# DevModule.net
KiCad netlist of a schematic drawn in Altium Designer
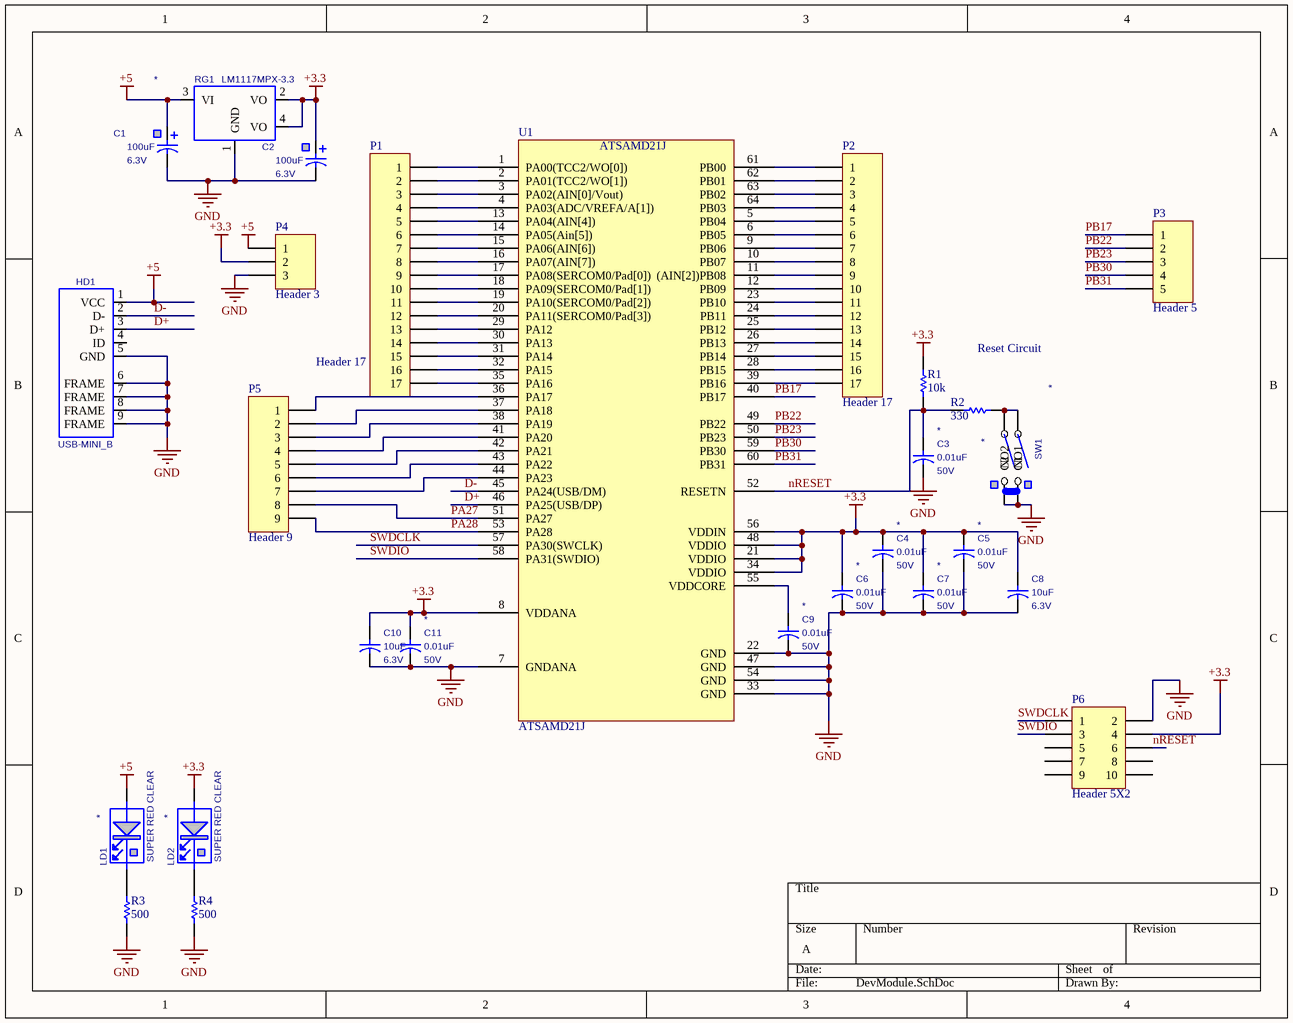
[diagram p0: DevModule.SchDoc]

(export (version "E")
  (design (tool "Eeschema 10.0.6"))
  (components
    (comp (ref "C1")
      (value "100uF")
      (footprint "100uF_6.3V_Tant_0805")
      (description "Capacitor")
      (fields
        (field (name "TOLERANCE") "+/- 20%")
        (field (name "VOLTAGE") "6.3V")
        (field (name "Comment") "100UF_TANT_6.3V_0805")
        (field (name "CHECKEDBY") "Sam Rhoufiry")
      )
      (libsource (lib "C") (part "100UF_TANT_6.3V_0805"))
    )
    (comp (ref "C2")
      (value "100uF")
      (footprint "100uF_6.3V_Tant_0805")
      (description "Capacitor")
      (fields
        (field (name "TOLERANCE") "+/- 20%")
        (field (name "VOLTAGE") "6.3V")
        (field (name "Comment") "100UF_TANT_6.3V_0805")
        (field (name "CHECKEDBY") "Sam Rhoufiry")
      )
      (libsource (lib "C") (part "100UF_TANT_6.3V_0805"))
    )
    (comp (ref "C3")
      (value "0.01uF")
      (footprint "RC0603REFLOW-IPC")
      (description "Capacitor")
      (fields
        (field (name "TOLERANCE") "+/- 10%")
        (field (name "DNS") "*")
        (field (name "VOLTAGE") "50V")
        (field (name "Comment") "0.01UF_0603REFLOW")
        (field (name "CHECKEDBY") "*")
      )
      (libsource (lib "C") (part "0.01UF_0603REFLOW"))
    )
    (comp (ref "C4")
      (value "0.01uF")
      (footprint "RC0603REFLOW-IPC")
      (description "Capacitor")
      (fields
        (field (name "TOLERANCE") "+/- 10%")
        (field (name "DNS") "*")
        (field (name "VOLTAGE") "50V")
        (field (name "Comment") "0.01UF_0603REFLOW")
        (field (name "CHECKEDBY") "*")
      )
      (libsource (lib "C") (part "0.01UF_0603REFLOW"))
    )
    (comp (ref "C5")
      (value "0.01uF")
      (footprint "RC0603REFLOW-IPC")
      (description "Capacitor")
      (fields
        (field (name "TOLERANCE") "+/- 10%")
        (field (name "DNS") "*")
        (field (name "VOLTAGE") "50V")
        (field (name "Comment") "0.01UF_0603REFLOW")
        (field (name "CHECKEDBY") "*")
      )
      (libsource (lib "C") (part "0.01UF_0603REFLOW"))
    )
    (comp (ref "C6")
      (value "0.01uF")
      (footprint "RC0603REFLOW-IPC")
      (description "Capacitor")
      (fields
        (field (name "TOLERANCE") "+/- 10%")
        (field (name "DNS") "*")
        (field (name "VOLTAGE") "50V")
        (field (name "Comment") "0.01UF_0603REFLOW")
        (field (name "CHECKEDBY") "*")
      )
      (libsource (lib "C") (part "0.01UF_0603REFLOW"))
    )
    (comp (ref "C7")
      (value "0.01uF")
      (footprint "RC0603REFLOW-IPC")
      (description "Capacitor")
      (fields
        (field (name "TOLERANCE") "+/- 10%")
        (field (name "DNS") "*")
        (field (name "VOLTAGE") "50V")
        (field (name "Comment") "0.01UF_0603REFLOW")
        (field (name "CHECKEDBY") "*")
      )
      (libsource (lib "C") (part "0.01UF_0603REFLOW"))
    )
    (comp (ref "C8")
      (value "10uF")
      (footprint "1206_NP_CAP")
      (fields
        (field (name "TOLERANCE") "-20%, +80%")
        (field (name "VOLTAGE") "6.3V")
        (field (name "Comment") "10uF_Ceramic_6.3V")
        (field (name "CHECKEDBY") "gdeguzman")
        (field (name "LASTUPDATEDBY") "Mike Tyger")
      )
      (libsource (lib "bome") (part "10uF_Ceramic_6.3V"))
    )
    (comp (ref "C9")
      (value "0.01uF")
      (footprint "RC0603REFLOW-IPC")
      (description "Capacitor")
      (fields
        (field (name "TOLERANCE") "+/- 10%")
        (field (name "DNS") "*")
        (field (name "VOLTAGE") "50V")
        (field (name "Comment") "0.01UF_0603REFLOW")
        (field (name "CHECKEDBY") "*")
      )
      (libsource (lib "C") (part "0.01UF_0603REFLOW"))
    )
    (comp (ref "C10")
      (value "10uF")
      (footprint "1206_NP_CAP")
      (fields
        (field (name "TOLERANCE") "-20%, +80%")
        (field (name "VOLTAGE") "6.3V")
        (field (name "Comment") "10uF_Ceramic_6.3V")
        (field (name "CHECKEDBY") "gdeguzman")
        (field (name "LASTUPDATEDBY") "Mike Tyger")
      )
      (libsource (lib "bome") (part "10uF_Ceramic_6.3V"))
    )
    (comp (ref "C11")
      (value "0.01uF")
      (footprint "RC0603REFLOW-IPC")
      (description "Capacitor")
      (fields
        (field (name "TOLERANCE") "+/- 10%")
        (field (name "DNS") "*")
        (field (name "VOLTAGE") "50V")
        (field (name "Comment") "0.01UF_0603REFLOW")
        (field (name "CHECKEDBY") "*")
      )
      (libsource (lib "C") (part "0.01UF_0603REFLOW"))
    )
    (comp (ref "HD1")
      (value "USB-MINI_B")
      (footprint "HD_USB_MINI_B")
      (description "Header")
      (fields (field (name "CHECKEDBY") "T. Hayes"))
      (libsource (lib "HD") (part "USB-MINI_B"))
    )
    (comp (ref "LD1")
      (value "0603_RED")
      (footprint "LED0603REFLOW-IPC-COLOR")
      (description "LED")
      (fields
        (field (name "DNS") "*")
        (field (name "COLOR") "SUPER RED CLEAR")
        (field (name "CHECKEDBY") "Elton John")
      )
      (libsource (lib "bome") (part "0603_RED"))
    )
    (comp (ref "LD2")
      (value "0603_RED")
      (footprint "LED0603REFLOW-IPC-COLOR")
      (description "LED")
      (fields
        (field (name "DNS") "*")
        (field (name "COLOR") "SUPER RED CLEAR")
        (field (name "CHECKEDBY") "Elton John")
      )
      (libsource (lib "bome") (part "0603_RED"))
    )
    (comp (ref "P1")
      (value "Header 17")
      (footprint "HDR1X17")
      (description "Header, 17-Pin")
      (fields (field (name "PUBLISHER") "Altium Limited"))
      (libsource (lib "") (part "Header 17_1"))
    )
    (comp (ref "P2")
      (value "Header 17")
      (footprint "HDR1X17")
      (description "Header, 17-Pin")
      (fields (field (name "PUBLISHER") "Altium Limited"))
      (libsource (lib "Miscellaneous Connectors") (part "Header 17"))
    )
    (comp (ref "P3")
      (value "Header 5")
      (footprint "HDR1X5")
      (description "Header, 5-Pin")
      (fields (field (name "PUBLISHER") "Altium Limited"))
      (libsource (lib "Miscellaneous Connectors") (part "Header 5"))
    )
    (comp (ref "P4")
      (value "Header 3")
      (footprint "HDR1X3")
      (description "Header, 3-Pin")
      (fields (field (name "PUBLISHER") "Altium Limited"))
      (libsource (lib "Miscellaneous Connectors") (part "Header 3"))
    )
    (comp (ref "P5")
      (value "Header 9")
      (footprint "HDR1X9")
      (description "Header, 9-Pin")
      (fields (field (name "PUBLISHER") "Altium Limited"))
      (libsource (lib "Miscellaneous Connectors") (part "Header 9"))
    )
    (comp (ref "P6")
      (value "Header 5X2")
      (footprint "HDR2X5")
      (description "Header, 5-Pin, Dual row")
      (fields (field (name "PUBLISHER") "Altium Limited"))
      (libsource (lib "Miscellaneous Connectors") (part "Header 5X2"))
    )
    (comp (ref "R1")
      (value "10k")
      (footprint "RESC2012L")
      (description "Semiconductor Resistor")
      (fields (field (name "Comment") "Res Semi") (field (name "PUBLISHER") "Altium Limited"))
      (libsource (lib "Miscellaneous Devices") (part "Res Semi"))
    )
    (comp (ref "R2")
      (value "330")
      (footprint "RESC2012L")
      (description "Semiconductor Resistor")
      (fields (field (name "Comment") "Res Semi") (field (name "PUBLISHER") "Altium Limited"))
      (libsource (lib "Miscellaneous Devices") (part "Res Semi"))
    )
    (comp (ref "R3")
      (value "500")
      (footprint "RESC2012L")
      (description "Semiconductor Resistor")
      (fields (field (name "Comment") "Res Semi") (field (name "PUBLISHER") "Altium Limited"))
      (libsource (lib "Miscellaneous Devices") (part "Res Semi"))
    )
    (comp (ref "R4")
      (value "500")
      (footprint "RESC2012L")
      (description "Semiconductor Resistor")
      (fields (field (name "Comment") "Res Semi") (field (name "PUBLISHER") "Altium Limited"))
      (libsource (lib "Miscellaneous Devices") (part "Res Semi"))
    )
    (comp (ref "RG1")
      (value "LM1117MPX-3.3")
      (footprint "SOT223REFLOW")
      (description "Regulator")
      (fields
        (field (name "VOLTAGE") "3.3V")
        (field (name "DNS") "*")
        (field (name "Comment") "LM1117SPX-3.3_SOT223")
        (field (name "CHECKEDBY") "B. Lyon")
      )
      (libsource (lib "RG") (part "LM1117SPX-3.3_SOT223"))
    )
    (comp (ref "SW1")
      (value "SW-PCB-4P-6MM")
      (footprint "SW-PCB-4PIN")
      (description "Switch")
      (fields (field (name "DNS") "*") (field (name "ALTIUM_VALUE") "*") (field (name "CHECKEDBY") "*"))
      (libsource (lib "SW") (part "SW-PCB-4P-6MM"))
    )
    (comp (ref "U1")
      (value "ATSAMD21J")
      (footprint "64-TQFP")
      (libsource (lib "mainBoardLib") (part "ATSAMD21J"))
    )
  )
  (nets
    (net (code "1") (name "+3.3") (class "Default")
      (node (ref "C10") (pin "1") (pinfunction "pin1_1") (pintype "passive"))
      (node (ref "C11") (pin "1") (pinfunction "pin1_1") (pintype "passive"))
      (node (ref "C2") (pin "1") (pinfunction "+_1") (pintype "passive"))
      (node (ref "C4") (pin "1") (pinfunction "pin1_1") (pintype "passive"))
      (node (ref "C5") (pin "1") (pinfunction "pin1_1") (pintype "passive"))
      (node (ref "C6") (pin "1") (pinfunction "pin1_1") (pintype "passive"))
      (node (ref "C7") (pin "1") (pinfunction "pin1_1") (pintype "passive"))
      (node (ref "C8") (pin "1") (pinfunction "pin1_1") (pintype "passive"))
      (node (ref "LD2") (pin "2") (pinfunction "ANODE_2") (pintype "passive"))
      (node (ref "P4") (pin "2") (pinfunction "2_2") (pintype "passive"))
      (node (ref "P6") (pin "4") (pinfunction "4_4") (pintype "passive"))
      (node (ref "R1") (pin "2") (pinfunction "2_2") (pintype "passive"))
      (node (ref "RG1") (pin "2") (pinfunction "VO_2") (pintype "passive"))
      (node (ref "RG1") (pin "4") (pinfunction "VO_4") (pintype "passive"))
      (node (ref "U1") (pin "21") (pinfunction "VDDIO_21") (pintype "passive"))
      (node (ref "U1") (pin "34") (pinfunction "VDDIO_34") (pintype "passive"))
      (node (ref "U1") (pin "48") (pinfunction "VDDIO_48") (pintype "passive"))
      (node (ref "U1") (pin "56") (pinfunction "VDDIN_56") (pintype "passive"))
      (node (ref "U1") (pin "8") (pinfunction "VDDANA_8") (pintype "passive"))
    )
    (net (code "2") (name "+5") (class "Default")
      (node (ref "C1") (pin "1") (pinfunction "+_1") (pintype "passive"))
      (node (ref "HD1") (pin "1") (pinfunction "VCC_1") (pintype "passive"))
      (node (ref "LD1") (pin "2") (pinfunction "ANODE_2") (pintype "passive"))
      (node (ref "P4") (pin "1") (pinfunction "1_1") (pintype "passive"))
      (node (ref "RG1") (pin "3") (pinfunction "VI_3") (pintype "passive"))
    )
    (net (code "3") (name "/D+") (class "Default")
      (node (ref "HD1") (pin "3") (pinfunction "D+_3") (pintype "passive"))
      (node (ref "U1") (pin "46") (pinfunction "PA25(USB/DP)_46") (pintype "passive"))
    )
    (net (code "4") (name "/D-") (class "Default")
      (node (ref "HD1") (pin "2") (pinfunction "D-_2") (pintype "passive"))
      (node (ref "U1") (pin "45") (pinfunction "PA24(USB/DM)_45") (pintype "passive"))
    )
    (net (code "5") (name "/PA27") (class "Default")
      (node (ref "P5") (pin "8") (pinfunction "8_8") (pintype "passive"))
      (node (ref "U1") (pin "51") (pinfunction "PA27_51") (pintype "passive"))
    )
    (net (code "6") (name "/PA28") (class "Default")
      (node (ref "P5") (pin "9") (pinfunction "9_9") (pintype "passive"))
      (node (ref "U1") (pin "53") (pinfunction "PA28_53") (pintype "passive"))
    )
    (net (code "7") (name "/PB17") (class "Default")
      (node (ref "P3") (pin "1") (pinfunction "1_1") (pintype "passive"))
      (node (ref "U1") (pin "40") (pinfunction "PB17_40") (pintype "passive"))
    )
    (net (code "8") (name "/PB22") (class "Default")
      (node (ref "P3") (pin "2") (pinfunction "2_2") (pintype "passive"))
      (node (ref "U1") (pin "49") (pinfunction "PB22_49") (pintype "passive"))
    )
    (net (code "9") (name "/PB23") (class "Default")
      (node (ref "P3") (pin "3") (pinfunction "3_3") (pintype "passive"))
      (node (ref "U1") (pin "50") (pinfunction "PB23_50") (pintype "passive"))
    )
    (net (code "10") (name "/PB30") (class "Default")
      (node (ref "P3") (pin "4") (pinfunction "4_4") (pintype "passive"))
      (node (ref "U1") (pin "59") (pinfunction "PB30_59") (pintype "passive"))
    )
    (net (code "11") (name "/PB31") (class "Default")
      (node (ref "P3") (pin "5") (pinfunction "5_5") (pintype "passive"))
      (node (ref "U1") (pin "60") (pinfunction "PB31_60") (pintype "passive"))
    )
    (net (code "12") (name "/SWDCLK") (class "Default")
      (node (ref "P6") (pin "1") (pinfunction "1_1") (pintype "passive"))
      (node (ref "U1") (pin "57") (pinfunction "PA30(SWCLK)_57") (pintype "passive"))
    )
    (net (code "13") (name "/SWDIO") (class "Default")
      (node (ref "P6") (pin "3") (pinfunction "3_3") (pintype "passive"))
      (node (ref "U1") (pin "58") (pinfunction "PA31(SWDIO)_58") (pintype "passive"))
    )
    (net (code "14") (name "/nRESET") (class "Default")
      (node (ref "C3") (pin "1") (pinfunction "pin1_1") (pintype "passive"))
      (node (ref "P6") (pin "6") (pinfunction "6_6") (pintype "passive"))
      (node (ref "R1") (pin "1") (pinfunction "1_1") (pintype "passive"))
      (node (ref "R2") (pin "1") (pinfunction "1_1") (pintype "passive"))
      (node (ref "U1") (pin "52") (pinfunction "RESETN_52") (pintype "passive"))
    )
    (net (code "15") (name "GND") (class "Default")
      (node (ref "C1") (pin "2") (pinfunction "-_2") (pintype "passive"))
      (node (ref "C10") (pin "2") (pinfunction "pin2_2") (pintype "passive"))
      (node (ref "C11") (pin "2") (pinfunction "pin2_2") (pintype "passive"))
      (node (ref "C2") (pin "2") (pinfunction "-_2") (pintype "passive"))
      (node (ref "C3") (pin "2") (pinfunction "pin2_2") (pintype "passive"))
      (node (ref "C4") (pin "2") (pinfunction "pin2_2") (pintype "passive"))
      (node (ref "C5") (pin "2") (pinfunction "pin2_2") (pintype "passive"))
      (node (ref "C6") (pin "2") (pinfunction "pin2_2") (pintype "passive"))
      (node (ref "C7") (pin "2") (pinfunction "pin2_2") (pintype "passive"))
      (node (ref "C8") (pin "2") (pinfunction "pin2_2") (pintype "passive"))
      (node (ref "C9") (pin "2") (pinfunction "pin2_2") (pintype "passive"))
      (node (ref "HD1") (pin "5") (pinfunction "GND_5") (pintype "passive"))
      (node (ref "HD1") (pin "6") (pinfunction "FRAME_6") (pintype "passive"))
      (node (ref "HD1") (pin "7") (pinfunction "FRAME_7") (pintype "passive"))
      (node (ref "HD1") (pin "8") (pinfunction "FRAME_8") (pintype "passive"))
      (node (ref "HD1") (pin "9") (pinfunction "FRAME_9") (pintype "passive"))
      (node (ref "P4") (pin "3") (pinfunction "3_3") (pintype "passive"))
      (node (ref "P6") (pin "2") (pinfunction "2_2") (pintype "passive"))
      (node (ref "R3") (pin "1") (pinfunction "1_1") (pintype "passive"))
      (node (ref "R4") (pin "1") (pinfunction "1_1") (pintype "passive"))
      (node (ref "RG1") (pin "1") (pinfunction "GND_1") (pintype "passive"))
      (node (ref "SW1") (pin "1") (pinfunction "C1_1") (pintype "passive"))
      (node (ref "SW1") (pin "2") (pinfunction "C2_2") (pintype "passive"))
      (node (ref "U1") (pin "22") (pinfunction "GND_22") (pintype "passive"))
      (node (ref "U1") (pin "33") (pinfunction "GND_33") (pintype "passive"))
      (node (ref "U1") (pin "47") (pinfunction "GND_47") (pintype "passive"))
      (node (ref "U1") (pin "54") (pinfunction "GND_54") (pintype "passive"))
      (node (ref "U1") (pin "7") (pinfunction "GNDANA_7") (pintype "passive"))
    )
    (net (code "16") (name "Net-(C9-pin1)") (class "Default")
      (node (ref "C9") (pin "1") (pinfunction "pin1_1") (pintype "passive"))
      (node (ref "U1") (pin "55") (pinfunction "VDDCORE_55") (pintype "passive"))
    )
    (net (code "17") (name "Net-(LD1-CATHODE)") (class "Default")
      (node (ref "LD1") (pin "1") (pinfunction "CATHODE_1") (pintype "passive"))
      (node (ref "R3") (pin "2") (pinfunction "2_2") (pintype "passive"))
    )
    (net (code "18") (name "Net-(LD2-CATHODE)") (class "Default")
      (node (ref "LD2") (pin "1") (pinfunction "CATHODE_1") (pintype "passive"))
      (node (ref "R4") (pin "2") (pinfunction "2_2") (pintype "passive"))
    )
    (net (code "19") (name "Net-(SW1-NO1)") (class "Default")
      (node (ref "R2") (pin "2") (pinfunction "2_2") (pintype "passive"))
      (node (ref "SW1") (pin "3") (pinfunction "NO2_3") (pintype "passive"))
      (node (ref "SW1") (pin "4") (pinfunction "NO1_4") (pintype "passive"))
    )
    (net (code "20") (name "Net-(U1-(AIN[2])PB08)") (class "Default")
      (node (ref "P2") (pin "9") (pinfunction "9_9") (pintype "passive"))
      (node (ref "U1") (pin "11") (pinfunction "(AIN[2])PB08_11") (pintype "passive"))
    )
    (net (code "21") (name "Net-(U1-PA00(TCC2{slash}WO[0]))") (class "Default")
      (node (ref "P1") (pin "1") (pinfunction "1_1") (pintype "passive"))
      (node (ref "U1") (pin "1") (pinfunction "PA00(TCC2/WO[0])_1") (pintype "passive"))
    )
    (net (code "22") (name "Net-(U1-PA01(TCC2{slash}WO[1]))") (class "Default")
      (node (ref "P1") (pin "2") (pinfunction "2_2") (pintype "passive"))
      (node (ref "U1") (pin "2") (pinfunction "PA01(TCC2/WO[1])_2") (pintype "passive"))
    )
    (net (code "23") (name "Net-(U1-PA02(AIN[0]{slash}Vout))") (class "Default")
      (node (ref "P1") (pin "3") (pinfunction "3_3") (pintype "passive"))
      (node (ref "U1") (pin "3") (pinfunction "PA02(AIN[0]/Vout)_3") (pintype "passive"))
    )
    (net (code "24") (name "Net-(U1-PA03(ADC{slash}VREFA{slash}A[1]))") (class "Default")
      (node (ref "P1") (pin "4") (pinfunction "4_4") (pintype "passive"))
      (node (ref "U1") (pin "4") (pinfunction "PA03(ADC/VREFA/A[1])_4") (pintype "passive"))
    )
    (net (code "25") (name "Net-(U1-PA04(AIN[4]))") (class "Default")
      (node (ref "P1") (pin "5") (pinfunction "5_5") (pintype "passive"))
      (node (ref "U1") (pin "13") (pinfunction "PA04(AIN[4])_13") (pintype "passive"))
    )
    (net (code "26") (name "Net-(U1-PA05(Ain[5]))") (class "Default")
      (node (ref "P1") (pin "6") (pinfunction "6_6") (pintype "passive"))
      (node (ref "U1") (pin "14") (pinfunction "PA05(Ain[5])_14") (pintype "passive"))
    )
    (net (code "27") (name "Net-(U1-PA06(AIN[6]))") (class "Default")
      (node (ref "P1") (pin "7") (pinfunction "7_7") (pintype "passive"))
      (node (ref "U1") (pin "15") (pinfunction "PA06(AIN[6])_15") (pintype "passive"))
    )
    (net (code "28") (name "Net-(U1-PA07(AIN[7]))") (class "Default")
      (node (ref "P1") (pin "8") (pinfunction "8_8") (pintype "passive"))
      (node (ref "U1") (pin "16") (pinfunction "PA07(AIN[7])_16") (pintype "passive"))
    )
    (net (code "29") (name "Net-(U1-PA08(SERCOM0{slash}Pad[0]))") (class "Default")
      (node (ref "P1") (pin "9") (pinfunction "9_9") (pintype "passive"))
      (node (ref "U1") (pin "17") (pinfunction "PA08(SERCOM0/Pad[0])_17") (pintype "passive"))
    )
    (net (code "30") (name "Net-(U1-PA09(SERCOM0{slash}Pad[1]))") (class "Default")
      (node (ref "P1") (pin "10") (pinfunction "10_10") (pintype "passive"))
      (node (ref "U1") (pin "18") (pinfunction "PA09(SERCOM0/Pad[1])_18") (pintype "passive"))
    )
    (net (code "31") (name "Net-(U1-PA10(SERCOM0{slash}Pad[2]))") (class "Default")
      (node (ref "P1") (pin "11") (pinfunction "11_11") (pintype "passive"))
      (node (ref "U1") (pin "19") (pinfunction "PA10(SERCOM0/Pad[2])_19") (pintype "passive"))
    )
    (net (code "32") (name "Net-(U1-PA11(SERCOM0{slash}Pad[3]))") (class "Default")
      (node (ref "P1") (pin "12") (pinfunction "12_12") (pintype "passive"))
      (node (ref "U1") (pin "20") (pinfunction "PA11(SERCOM0/Pad[3])_20") (pintype "passive"))
    )
    (net (code "33") (name "Net-(U1-PA12)") (class "Default")
      (node (ref "P1") (pin "13") (pinfunction "13_13") (pintype "passive"))
      (node (ref "U1") (pin "29") (pinfunction "PA12_29") (pintype "passive"))
    )
    (net (code "34") (name "Net-(U1-PA13)") (class "Default")
      (node (ref "P1") (pin "14") (pinfunction "14_14") (pintype "passive"))
      (node (ref "U1") (pin "30") (pinfunction "PA13_30") (pintype "passive"))
    )
    (net (code "35") (name "Net-(U1-PA14)") (class "Default")
      (node (ref "P1") (pin "15") (pinfunction "15_15") (pintype "passive"))
      (node (ref "U1") (pin "31") (pinfunction "PA14_31") (pintype "passive"))
    )
    (net (code "36") (name "Net-(U1-PA15)") (class "Default")
      (node (ref "P1") (pin "16") (pinfunction "16_16") (pintype "passive"))
      (node (ref "U1") (pin "32") (pinfunction "PA15_32") (pintype "passive"))
    )
    (net (code "37") (name "Net-(U1-PA16)") (class "Default")
      (node (ref "P1") (pin "17") (pinfunction "17_17") (pintype "passive"))
      (node (ref "U1") (pin "35") (pinfunction "PA16_35") (pintype "passive"))
    )
    (net (code "38") (name "Net-(U1-PA17)") (class "Default")
      (node (ref "P5") (pin "1") (pinfunction "1_1") (pintype "passive"))
      (node (ref "U1") (pin "36") (pinfunction "PA17_36") (pintype "passive"))
    )
    (net (code "39") (name "Net-(U1-PA18)") (class "Default")
      (node (ref "P5") (pin "2") (pinfunction "2_2") (pintype "passive"))
      (node (ref "U1") (pin "37") (pinfunction "PA18_37") (pintype "passive"))
    )
    (net (code "40") (name "Net-(U1-PA19)") (class "Default")
      (node (ref "P5") (pin "3") (pinfunction "3_3") (pintype "passive"))
      (node (ref "U1") (pin "38") (pinfunction "PA19_38") (pintype "passive"))
    )
    (net (code "41") (name "Net-(U1-PA20)") (class "Default")
      (node (ref "P5") (pin "4") (pinfunction "4_4") (pintype "passive"))
      (node (ref "U1") (pin "41") (pinfunction "PA20_41") (pintype "passive"))
    )
    (net (code "42") (name "Net-(U1-PA21)") (class "Default")
      (node (ref "P5") (pin "5") (pinfunction "5_5") (pintype "passive"))
      (node (ref "U1") (pin "42") (pinfunction "PA21_42") (pintype "passive"))
    )
    (net (code "43") (name "Net-(U1-PA22)") (class "Default")
      (node (ref "P5") (pin "6") (pinfunction "6_6") (pintype "passive"))
      (node (ref "U1") (pin "43") (pinfunction "PA22_43") (pintype "passive"))
    )
    (net (code "44") (name "Net-(U1-PA23)") (class "Default")
      (node (ref "P5") (pin "7") (pinfunction "7_7") (pintype "passive"))
      (node (ref "U1") (pin "44") (pinfunction "PA23_44") (pintype "passive"))
    )
    (net (code "45") (name "Net-(U1-PB00)") (class "Default")
      (node (ref "P2") (pin "1") (pinfunction "1_1") (pintype "passive"))
      (node (ref "U1") (pin "61") (pinfunction "PB00_61") (pintype "passive"))
    )
    (net (code "46") (name "Net-(U1-PB01)") (class "Default")
      (node (ref "P2") (pin "2") (pinfunction "2_2") (pintype "passive"))
      (node (ref "U1") (pin "62") (pinfunction "PB01_62") (pintype "passive"))
    )
    (net (code "47") (name "Net-(U1-PB02)") (class "Default")
      (node (ref "P2") (pin "3") (pinfunction "3_3") (pintype "passive"))
      (node (ref "U1") (pin "63") (pinfunction "PB02_63") (pintype "passive"))
    )
    (net (code "48") (name "Net-(U1-PB03)") (class "Default")
      (node (ref "P2") (pin "4") (pinfunction "4_4") (pintype "passive"))
      (node (ref "U1") (pin "64") (pinfunction "PB03_64") (pintype "passive"))
    )
    (net (code "49") (name "Net-(U1-PB04)") (class "Default")
      (node (ref "P2") (pin "5") (pinfunction "5_5") (pintype "passive"))
      (node (ref "U1") (pin "5") (pinfunction "PB04_5") (pintype "passive"))
    )
    (net (code "50") (name "Net-(U1-PB05)") (class "Default")
      (node (ref "P2") (pin "6") (pinfunction "6_6") (pintype "passive"))
      (node (ref "U1") (pin "6") (pinfunction "PB05_6") (pintype "passive"))
    )
    (net (code "51") (name "Net-(U1-PB06)") (class "Default")
      (node (ref "P2") (pin "7") (pinfunction "7_7") (pintype "passive"))
      (node (ref "U1") (pin "9") (pinfunction "PB06_9") (pintype "passive"))
    )
    (net (code "52") (name "Net-(U1-PB07)") (class "Default")
      (node (ref "P2") (pin "8") (pinfunction "8_8") (pintype "passive"))
      (node (ref "U1") (pin "10") (pinfunction "PB07_10") (pintype "passive"))
    )
    (net (code "53") (name "Net-(U1-PB09)") (class "Default")
      (node (ref "P2") (pin "10") (pinfunction "10_10") (pintype "passive"))
      (node (ref "U1") (pin "12") (pinfunction "PB09_12") (pintype "passive"))
    )
    (net (code "54") (name "Net-(U1-PB10)") (class "Default")
      (node (ref "P2") (pin "11") (pinfunction "11_11") (pintype "passive"))
      (node (ref "U1") (pin "23") (pinfunction "PB10_23") (pintype "passive"))
    )
    (net (code "55") (name "Net-(U1-PB11)") (class "Default")
      (node (ref "P2") (pin "12") (pinfunction "12_12") (pintype "passive"))
      (node (ref "U1") (pin "24") (pinfunction "PB11_24") (pintype "passive"))
    )
    (net (code "56") (name "Net-(U1-PB12)") (class "Default")
      (node (ref "P2") (pin "13") (pinfunction "13_13") (pintype "passive"))
      (node (ref "U1") (pin "25") (pinfunction "PB12_25") (pintype "passive"))
    )
    (net (code "57") (name "Net-(U1-PB13)") (class "Default")
      (node (ref "P2") (pin "14") (pinfunction "14_14") (pintype "passive"))
      (node (ref "U1") (pin "26") (pinfunction "PB13_26") (pintype "passive"))
    )
    (net (code "58") (name "Net-(U1-PB14)") (class "Default")
      (node (ref "P2") (pin "15") (pinfunction "15_15") (pintype "passive"))
      (node (ref "U1") (pin "27") (pinfunction "PB14_27") (pintype "passive"))
    )
    (net (code "59") (name "Net-(U1-PB15)") (class "Default")
      (node (ref "P2") (pin "16") (pinfunction "16_16") (pintype "passive"))
      (node (ref "U1") (pin "28") (pinfunction "PB15_28") (pintype "passive"))
    )
    (net (code "60") (name "Net-(U1-PB16)") (class "Default")
      (node (ref "P2") (pin "17") (pinfunction "17_17") (pintype "passive"))
      (node (ref "U1") (pin "39") (pinfunction "PB16_39") (pintype "passive"))
    )
    (net (code "61") (name "unconnected-(HD1-ID-Pad4)") (class "Default")
      (node (ref "HD1") (pin "4") (pinfunction "ID_4") (pintype "passive"))
    )
    (net (code "62") (name "unconnected-(HD1-Pad10)") (class "Default")
      (node (ref "HD1") (pin "10") (pintype "passive"))
    )
    (net (code "63") (name "unconnected-(HD1-Pad11)") (class "Default")
      (node (ref "HD1") (pin "11") (pintype "passive"))
    )
    (net (code "64") (name "unconnected-(P6-Pad5)") (class "Default")
      (node (ref "P6") (pin "5") (pinfunction "5_5") (pintype "passive"))
    )
    (net (code "65") (name "unconnected-(P6-Pad7)") (class "Default")
      (node (ref "P6") (pin "7") (pinfunction "7_7") (pintype "passive"))
    )
    (net (code "66") (name "unconnected-(P6-Pad8)") (class "Default")
      (node (ref "P6") (pin "8") (pinfunction "8_8") (pintype "passive"))
    )
    (net (code "67") (name "unconnected-(P6-Pad9)") (class "Default")
      (node (ref "P6") (pin "9") (pinfunction "9_9") (pintype "passive"))
    )
    (net (code "68") (name "unconnected-(P6-Pad10)") (class "Default")
      (node (ref "P6") (pin "10") (pinfunction "10_10") (pintype "passive"))
    )
  )
)
